# Encoder_Fin_-_MCU.net
KiCad netlist of a schematic drawn in Altium Designer
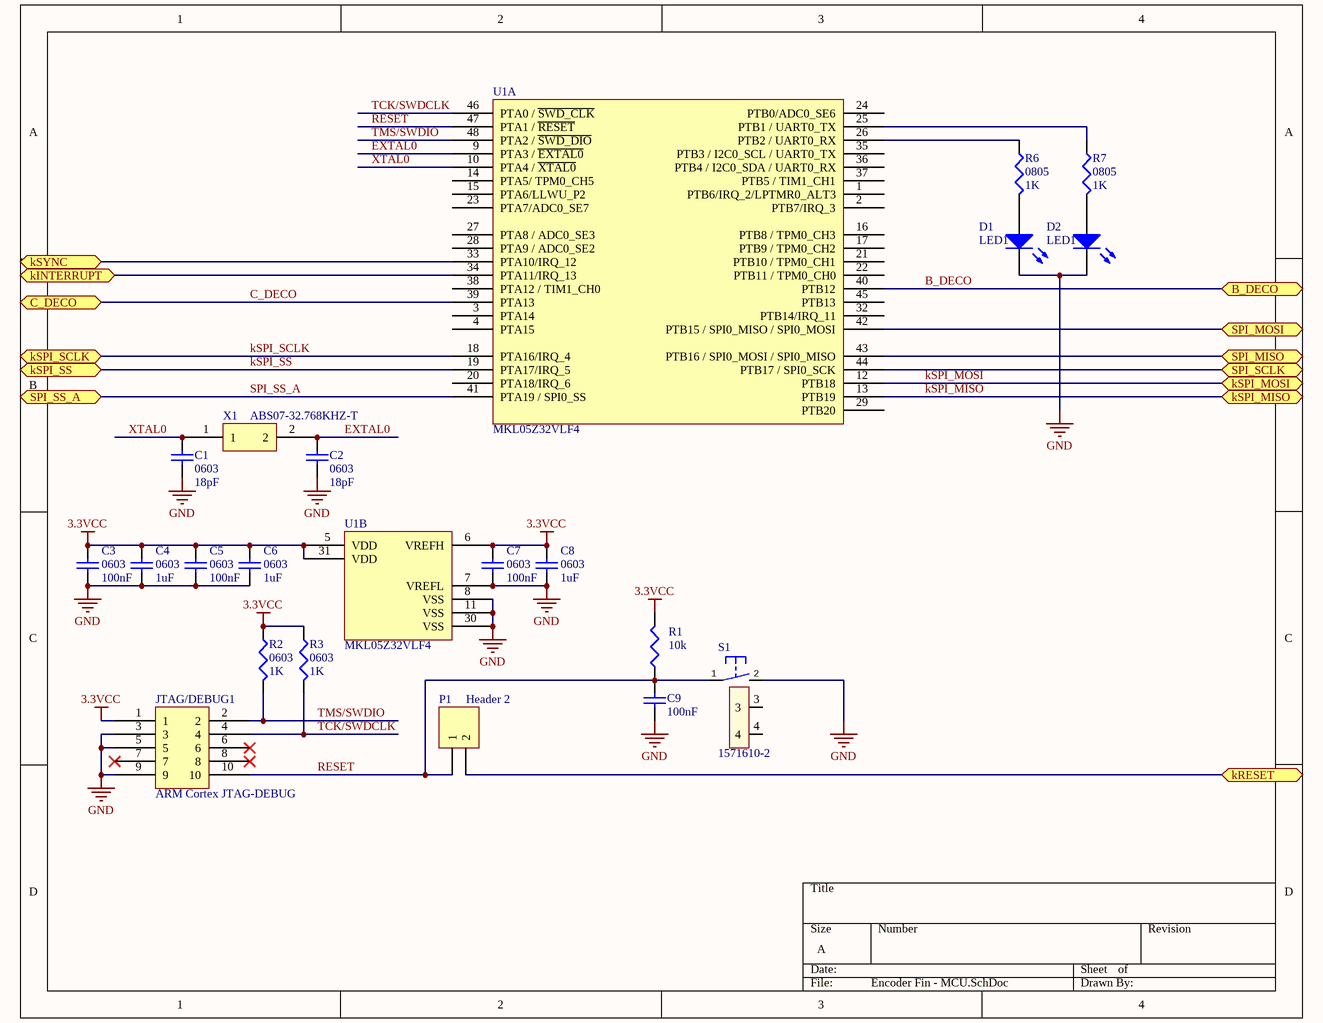
[diagram p0: Encoder Fin - MCU.SchDoc]

(export (version "E")
  (design (tool "Eeschema 10.0.6"))
  (components
    (comp (ref "C1")
      (value "0603")
      (footprint "1608[0603]")
      (description "Capacitor (Semiconductor SIM Model)")
      (fields (field (name "ALTIUM_VALUE") "18pF") (field (name "PUBLISHER") "Altium Limited"))
      (libsource (lib "Miscellaneous Devices") (part "Cap Semi"))
    )
    (comp (ref "C2")
      (value "0603")
      (footprint "1608[0603]")
      (description "Capacitor (Semiconductor SIM Model)")
      (fields (field (name "ALTIUM_VALUE") "18pF") (field (name "PUBLISHER") "Altium Limited"))
      (libsource (lib "Miscellaneous Devices") (part "Cap Semi"))
    )
    (comp (ref "C3")
      (value "0603")
      (footprint "1608[0603]")
      (description "Capacitor (Semiconductor SIM Model)")
      (fields (field (name "ALTIUM_VALUE") "100nF") (field (name "PUBLISHER") "Altium Limited"))
      (libsource (lib "Miscellaneous Devices") (part "Cap Semi"))
    )
    (comp (ref "C4")
      (value "0603")
      (footprint "1608[0603]")
      (description "Capacitor (Semiconductor SIM Model)")
      (fields (field (name "ALTIUM_VALUE") "1uF") (field (name "PUBLISHER") "Altium Limited"))
      (libsource (lib "Miscellaneous Devices") (part "Cap Semi"))
    )
    (comp (ref "C5")
      (value "0603")
      (footprint "1608[0603]")
      (description "Capacitor (Semiconductor SIM Model)")
      (fields (field (name "ALTIUM_VALUE") "100nF") (field (name "PUBLISHER") "Altium Limited"))
      (libsource (lib "Miscellaneous Devices") (part "Cap Semi"))
    )
    (comp (ref "C6")
      (value "0603")
      (footprint "1608[0603]")
      (description "Capacitor (Semiconductor SIM Model)")
      (fields (field (name "ALTIUM_VALUE") "1uF") (field (name "PUBLISHER") "Altium Limited"))
      (libsource (lib "Miscellaneous Devices") (part "Cap Semi"))
    )
    (comp (ref "C7")
      (value "0603")
      (footprint "1608[0603]")
      (description "Capacitor (Semiconductor SIM Model)")
      (fields (field (name "ALTIUM_VALUE") "100nF") (field (name "PUBLISHER") "Altium Limited"))
      (libsource (lib "Miscellaneous Devices") (part "Cap Semi"))
    )
    (comp (ref "C8")
      (value "0603")
      (footprint "1608[0603]")
      (description "Capacitor (Semiconductor SIM Model)")
      (fields (field (name "ALTIUM_VALUE") "1uF") (field (name "PUBLISHER") "Altium Limited"))
      (libsource (lib "Miscellaneous Devices") (part "Cap Semi"))
    )
    (comp (ref "C9")
      (value "100nF")
      (footprint "1608[0603]")
      (description "Capacitor (Semiconductor SIM Model)")
      (fields (field (name "Comment") "Cap Semi") (field (name "PUBLISHER") "Altium Limited"))
      (libsource (lib "Miscellaneous Devices") (part "Cap Semi"))
    )
    (comp (ref "D1")
      (value "LED1")
      (footprint "SM 0805 polarized")
      (description "Typical RED GaAs LED")
      (fields (field (name "PUBLISHER") "Altium Limited"))
      (libsource (lib "Miscellaneous Devices") (part "LED1"))
    )
    (comp (ref "D2")
      (value "LED1")
      (footprint "SM 0805 polarized")
      (description "Typical RED GaAs LED")
      (fields (field (name "PUBLISHER") "Altium Limited"))
      (libsource (lib "Miscellaneous Devices") (part "LED1"))
    )
    (comp (ref "JTAG/DEBUG1")
      (value "ARM Cortex JTAG-DEBUG")
      (footprint "FTSH-105-XX-X-DV")
      (libsource (lib "Adams Altium Library") (part "ARM Cortex JTAG-DEBUG Header"))
    )
    (comp (ref "P1")
      (value "Header 2")
      (footprint "HDR1X2")
      (description "Header, 2-Pin")
      (fields (field (name "PUBLISHER") "Altium Limited"))
      (libsource (lib "Miscellaneous Connectors") (part "Header 2"))
    )
    (comp (ref "R1")
      (value "10k")
      (footprint "J1-0603")
      (description "Resistor")
      (fields (field (name "Comment") "Res3") (field (name "PUBLISHER") "Altium Limited"))
      (libsource (lib "Miscellaneous Devices") (part "Res3"))
    )
    (comp (ref "R2")
      (value "0603")
      (footprint "J1-0603")
      (description "Resistor")
      (fields (field (name "ALTIUM_VALUE") "1K") (field (name "PUBLISHER") "Altium Limited"))
      (libsource (lib "Miscellaneous Devices") (part "Res3"))
    )
    (comp (ref "R3")
      (value "0603")
      (footprint "J1-0603")
      (description "Resistor")
      (fields (field (name "ALTIUM_VALUE") "1K") (field (name "PUBLISHER") "Altium Limited"))
      (libsource (lib "Miscellaneous Devices") (part "Res3"))
    )
    (comp (ref "R6")
      (value "0805")
      (footprint "SM 0805 - gap trimmed")
      (description "Resistor")
      (fields (field (name "ALTIUM_VALUE") "1K") (field (name "PUBLISHER") "Altium Limited"))
      (libsource (lib "Miscellaneous Devices") (part "Res3"))
    )
    (comp (ref "R7")
      (value "0805")
      (footprint "SM 0805 - gap trimmed")
      (description "Resistor")
      (fields (field (name "ALTIUM_VALUE") "1K") (field (name "PUBLISHER") "Altium Limited"))
      (libsource (lib "Miscellaneous Devices") (part "Res3"))
    )
    (comp (ref "S1")
      (value "1571610-2")
      (footprint "B3F-31XX")
      (description "SWTCH Momentary Washable")
      (fields
        (field (name "MANUFACTURER") "Omron")
        (field (name "MANUFACTURER_1") "TE")
        (field (name "PUBLISHER") "UltiMachine")
      )
      (libsource (lib "ZMBo Schematic Library") (part "1571610-2_1"))
    )
    (comp (ref "U1")
      (value "MKL05Z32VLF4")
      (footprint "MKL05Z32VLF4")
      (description "ARM Cortex M0+")
      (libsource (lib "ExtruderFinLib") (part "MKL05Z32VLF4"))
    )
    (comp (ref "X1")
      (value "ABS07-32.768KHZ-T")
      (footprint "ABS07-32.768KHZ-T")
      (description "ABS07-32.768KHZ-T RTC Crystal Oscillator")
      (libsource (lib "Adams Altium Library") (part "ABS07-32.768KHZ-T"))
    )
  )
  (nets
    (net (code "1") (name "/B_DECO") (class "Default")
      (node (ref "U1") (pin "40") (pinfunction "PTB12_40") (pintype "passive"))
    )
    (net (code "2") (name "/C_DECO") (class "Default")
      (node (ref "U1") (pin "39") (pinfunction "PTA13_39") (pintype "passive"))
    )
    (net (code "3") (name "/EXTAL0") (class "Default")
      (node (ref "C2") (pin "1") (pinfunction "1_1") (pintype "passive"))
      (node (ref "U1") (pin "9") (pinfunction "PTA3_/_~{EXTAL0}_9") (pintype "passive"))
      (node (ref "X1") (pin "2") (pinfunction "2_2") (pintype "passive"))
    )
    (net (code "4") (name "/RESET") (class "Default")
      (node (ref "C9") (pin "2") (pinfunction "2_2") (pintype "passive"))
      (node (ref "JTAG/DEBUG1") (pin "10") (pinfunction "10_10") (pintype "passive"))
      (node (ref "P1") (pin "1") (pinfunction "1_1") (pintype "passive"))
      (node (ref "R1") (pin "1") (pinfunction "1_1") (pintype "passive"))
      (node (ref "S1") (pin "1") (pinfunction "P_1") (pintype "passive"))
      (node (ref "U1") (pin "47") (pinfunction "PTA1_/_~{RESET}_47") (pintype "passive"))
    )
    (net (code "5") (name "/SPI_MISO") (class "Default")
      (node (ref "U1") (pin "43") (pinfunction "PTB16_/_SPI0_MOSI_43") (pintype "passive"))
    )
    (net (code "6") (name "/SPI_MOSI") (class "Default")
      (node (ref "U1") (pin "42") (pinfunction "PTB15_/_SPI0_MISO_42") (pintype "passive"))
    )
    (net (code "7") (name "/SPI_SCLK") (class "Default")
      (node (ref "U1") (pin "44") (pinfunction "PTB17_/_SPI0_SCK_44") (pintype "passive"))
    )
    (net (code "8") (name "/SPI_SS_A") (class "Default")
      (node (ref "U1") (pin "41") (pinfunction "PTA19_/_SPI0_SS_41") (pintype "passive"))
    )
    (net (code "9") (name "/TCK{slash}SWDCLK") (class "Default")
      (node (ref "JTAG/DEBUG1") (pin "4") (pinfunction "4_4") (pintype "passive"))
      (node (ref "R3") (pin "2") (pinfunction "2_2") (pintype "passive"))
      (node (ref "U1") (pin "46") (pinfunction "PTA0_/_~{SWD_CLK}_46") (pintype "passive"))
    )
    (net (code "10") (name "/TMS{slash}SWDIO") (class "Default")
      (node (ref "JTAG/DEBUG1") (pin "2") (pinfunction "2_2") (pintype "passive"))
      (node (ref "R2") (pin "2") (pinfunction "2_2") (pintype "passive"))
      (node (ref "U1") (pin "48") (pinfunction "PTA2_/_~{SWD_DIO}_48") (pintype "passive"))
    )
    (net (code "11") (name "/XTAL0") (class "Default")
      (node (ref "C1") (pin "1") (pinfunction "1_1") (pintype "passive"))
      (node (ref "U1") (pin "10") (pinfunction "PTA4_/_~{XTAL0}_10") (pintype "passive"))
      (node (ref "X1") (pin "1") (pinfunction "1_1") (pintype "passive"))
    )
    (net (code "12") (name "/kINTERRUPT") (class "Default")
      (node (ref "U1") (pin "34") (pinfunction "PTA11/IRQ_13_34") (pintype "passive"))
    )
    (net (code "13") (name "/kRESET") (class "Default")
      (node (ref "P1") (pin "2") (pinfunction "2_2") (pintype "passive"))
    )
    (net (code "14") (name "/kSPI_MISO") (class "Default")
      (node (ref "U1") (pin "13") (pinfunction "PTB19_13") (pintype "passive"))
    )
    (net (code "15") (name "/kSPI_MOSI") (class "Default")
      (node (ref "U1") (pin "12") (pinfunction "PTB18_12") (pintype "passive"))
    )
    (net (code "16") (name "/kSPI_SCLK") (class "Default")
      (node (ref "U1") (pin "18") (pinfunction "PTA16/IRQ_4_18") (pintype "passive"))
    )
    (net (code "17") (name "/kSPI_SS") (class "Default")
      (node (ref "U1") (pin "19") (pinfunction "PTA17/IRQ_5_19") (pintype "passive"))
    )
    (net (code "18") (name "/kSYNC") (class "Default")
      (node (ref "U1") (pin "33") (pinfunction "PTA10/IRQ_12_33") (pintype "passive"))
    )
    (net (code "19") (name "3.3VCC") (class "Default")
      (node (ref "C3") (pin "2") (pinfunction "2_2") (pintype "passive"))
      (node (ref "C4") (pin "2") (pinfunction "2_2") (pintype "passive"))
      (node (ref "C5") (pin "2") (pinfunction "2_2") (pintype "passive"))
      (node (ref "C6") (pin "2") (pinfunction "2_2") (pintype "passive"))
      (node (ref "C7") (pin "1") (pinfunction "1_1") (pintype "passive"))
      (node (ref "C8") (pin "1") (pinfunction "1_1") (pintype "passive"))
      (node (ref "JTAG/DEBUG1") (pin "1") (pinfunction "1_1") (pintype "passive"))
      (node (ref "R1") (pin "2") (pinfunction "2_2") (pintype "passive"))
      (node (ref "R2") (pin "1") (pinfunction "1_1") (pintype "passive"))
      (node (ref "R3") (pin "1") (pinfunction "1_1") (pintype "passive"))
      (node (ref "U1") (pin "31") (pinfunction "VDD_31") (pintype "passive"))
      (node (ref "U1") (pin "5") (pinfunction "VDD_5") (pintype "passive"))
      (node (ref "U1") (pin "6") (pinfunction "VREFH_6") (pintype "passive"))
    )
    (net (code "20") (name "GND") (class "Default")
      (node (ref "C1") (pin "2") (pinfunction "2_2") (pintype "passive"))
      (node (ref "C2") (pin "2") (pinfunction "2_2") (pintype "passive"))
      (node (ref "C3") (pin "1") (pinfunction "1_1") (pintype "passive"))
      (node (ref "C4") (pin "1") (pinfunction "1_1") (pintype "passive"))
      (node (ref "C5") (pin "1") (pinfunction "1_1") (pintype "passive"))
      (node (ref "C6") (pin "1") (pinfunction "1_1") (pintype "passive"))
      (node (ref "C7") (pin "2") (pinfunction "2_2") (pintype "passive"))
      (node (ref "C8") (pin "2") (pinfunction "2_2") (pintype "passive"))
      (node (ref "C9") (pin "1") (pinfunction "1_1") (pintype "passive"))
      (node (ref "D1") (pin "1") (pinfunction "A_1") (pintype "passive"))
      (node (ref "D2") (pin "1") (pinfunction "A_1") (pintype "passive"))
      (node (ref "JTAG/DEBUG1") (pin "3") (pinfunction "3_3") (pintype "passive"))
      (node (ref "JTAG/DEBUG1") (pin "5") (pinfunction "5_5") (pintype "passive"))
      (node (ref "JTAG/DEBUG1") (pin "9") (pinfunction "9_9") (pintype "passive"))
      (node (ref "S1") (pin "2") (pinfunction "S_2") (pintype "passive"))
      (node (ref "U1") (pin "11") (pinfunction "VSS_11") (pintype "passive"))
      (node (ref "U1") (pin "30") (pinfunction "VSS_30") (pintype "passive"))
      (node (ref "U1") (pin "7") (pinfunction "VREFL_7") (pintype "passive"))
      (node (ref "U1") (pin "8") (pinfunction "VSS_8") (pintype "passive"))
    )
    (net (code "21") (name "Net-(D1-K)") (class "Default")
      (node (ref "D1") (pin "2") (pinfunction "K_2") (pintype "passive"))
      (node (ref "R6") (pin "2") (pinfunction "2_2") (pintype "passive"))
    )
    (net (code "22") (name "Net-(D2-K)") (class "Default")
      (node (ref "D2") (pin "2") (pinfunction "K_2") (pintype "passive"))
      (node (ref "R7") (pin "2") (pinfunction "2_2") (pintype "passive"))
    )
    (net (code "23") (name "Net-(U1A-PTB1_{slash}_UART0_TX)") (class "Default")
      (node (ref "R7") (pin "1") (pinfunction "1_1") (pintype "passive"))
      (node (ref "U1") (pin "25") (pinfunction "PTB1_/_UART0_TX_25") (pintype "passive"))
    )
    (net (code "24") (name "Net-(U1A-PTB2_{slash}_UART0_RX)") (class "Default")
      (node (ref "R6") (pin "1") (pinfunction "1_1") (pintype "passive"))
      (node (ref "U1") (pin "26") (pinfunction "PTB2_/_UART0_RX_26") (pintype "passive"))
    )
    (net (code "25") (name "unconnected-(JTAG/DEBUG1-Pad6)") (class "Default")
      (node (ref "JTAG/DEBUG1") (pin "6") (pinfunction "6_6") (pintype "passive+no_connect"))
    )
    (net (code "26") (name "unconnected-(JTAG/DEBUG1-Pad7)") (class "Default")
      (node (ref "JTAG/DEBUG1") (pin "7") (pinfunction "7_7") (pintype "passive+no_connect"))
    )
    (net (code "27") (name "unconnected-(JTAG/DEBUG1-Pad8)") (class "Default")
      (node (ref "JTAG/DEBUG1") (pin "8") (pinfunction "8_8") (pintype "passive+no_connect"))
    )
    (net (code "28") (name "unconnected-(S1-Pad3)") (class "Default")
      (node (ref "S1") (pin "3") (pinfunction "3_3") (pintype "power_in"))
    )
    (net (code "29") (name "unconnected-(S1-Pad4)") (class "Default")
      (node (ref "S1") (pin "4") (pinfunction "4_4") (pintype "power_in"))
    )
    (net (code "30") (name "unconnected-(U1A-PTA5{slash}LLWU_P{slash}RTC_CLK_IN-Pad14)") (class "Default")
      (node (ref "U1") (pin "14") (pinfunction "PTA5/LLWU_P/RTC_CLK_IN_14") (pintype "passive"))
    )
    (net (code "31") (name "unconnected-(U1A-PTA6{slash}LLWU_P2-Pad15)") (class "Default")
      (node (ref "U1") (pin "15") (pinfunction "PTA6/LLWU_P2_15") (pintype "passive"))
    )
    (net (code "32") (name "unconnected-(U1A-PTA7{slash}IRQ_7{slash}LLWU_P3-Pad23)") (class "Default")
      (node (ref "U1") (pin "23") (pinfunction "PTA7/IRQ_7/LLWU_P3_23") (pintype "passive"))
    )
    (net (code "33") (name "unconnected-(U1A-PTA8_{slash}_ADC0_SE3-Pad27)") (class "Default")
      (node (ref "U1") (pin "27") (pinfunction "PTA8_/_ADC0_SE3_27") (pintype "passive"))
    )
    (net (code "34") (name "unconnected-(U1A-PTA9_{slash}_ADC0_SE2-Pad28)") (class "Default")
      (node (ref "U1") (pin "28") (pinfunction "PTA9_/_ADC0_SE2_28") (pintype "passive"))
    )
    (net (code "35") (name "unconnected-(U1A-PTA12_{slash}_TIM1_CH0-Pad38)") (class "Default")
      (node (ref "U1") (pin "38") (pinfunction "PTA12_/_TIM1_CH0_38") (pintype "passive"))
    )
    (net (code "36") (name "unconnected-(U1A-PTA14-Pad3)") (class "Default")
      (node (ref "U1") (pin "3") (pinfunction "PTA14_3") (pintype "passive"))
    )
    (net (code "37") (name "unconnected-(U1A-PTA15-Pad4)") (class "Default")
      (node (ref "U1") (pin "4") (pinfunction "PTA15_4") (pintype "passive"))
    )
    (net (code "38") (name "unconnected-(U1A-PTA18{slash}IRQ_6-Pad20)") (class "Default")
      (node (ref "U1") (pin "20") (pinfunction "PTA18/IRQ_6_20") (pintype "passive"))
    )
    (net (code "39") (name "unconnected-(U1A-PTB0{slash}IRQ_8{slash}LLWU_P4-Pad24)") (class "Default")
      (node (ref "U1") (pin "24") (pinfunction "PTB0/IRQ_8/LLWU_P4_24") (pintype "passive"))
    )
    (net (code "40") (name "unconnected-(U1A-PTB3_{slash}_I2C0_SCL_{slash}_UART0_TX-Pad35)") (class "Default")
      (node (ref "U1") (pin "35") (pinfunction "PTB3_/_I2C0_SCL_/_UART0_TX_35") (pintype "passive"))
    )
    (net (code "41") (name "unconnected-(U1A-PTB4_{slash}_I2C0_SDA_{slash}_UART0_RX-Pad36)") (class "Default")
      (node (ref "U1") (pin "36") (pinfunction "PTB4_/_I2C0_SDA_/_UART0_RX_36") (pintype "passive"))
    )
    (net (code "42") (name "unconnected-(U1A-PTB5_{slash}_TIM1_CH1-Pad37)") (class "Default")
      (node (ref "U1") (pin "37") (pinfunction "PTB5_/_TIM1_CH1_37") (pintype "passive"))
    )
    (net (code "43") (name "unconnected-(U1A-PTB6{slash}IRQ_2{slash}LPTMR0_ALT3-Pad1)") (class "Default")
      (node (ref "U1") (pin "1") (pinfunction "PTB6/IRQ_2/LPTMR0_ALT3_1") (pintype "passive"))
    )
    (net (code "44") (name "unconnected-(U1A-PTB7{slash}IRQ_3-Pad2)") (class "Default")
      (node (ref "U1") (pin "2") (pinfunction "PTB7/IRQ_3_2") (pintype "passive"))
    )
    (net (code "45") (name "unconnected-(U1A-PTB8_{slash}_TPM0_CH3-Pad16)") (class "Default")
      (node (ref "U1") (pin "16") (pinfunction "PTB8_/_TPM0_CH3_16") (pintype "passive"))
    )
    (net (code "46") (name "unconnected-(U1A-PTB9_{slash}_TPM0_CH2-Pad17)") (class "Default")
      (node (ref "U1") (pin "17") (pinfunction "PTB9_/_TPM0_CH2_17") (pintype "passive"))
    )
    (net (code "47") (name "unconnected-(U1A-PTB10_{slash}_TPM0_CH1-Pad21)") (class "Default")
      (node (ref "U1") (pin "21") (pinfunction "PTB10_/_TPM0_CH1_21") (pintype "passive"))
    )
    (net (code "48") (name "unconnected-(U1A-PTB11_{slash}_TPM0_CH0-Pad22)") (class "Default")
      (node (ref "U1") (pin "22") (pinfunction "PTB11_/_TPM0_CH0_22") (pintype "passive"))
    )
    (net (code "49") (name "unconnected-(U1A-PTB13-Pad45)") (class "Default")
      (node (ref "U1") (pin "45") (pinfunction "PTB13_45") (pintype "passive"))
    )
    (net (code "50") (name "unconnected-(U1A-PTB14{slash}IRQ_11-Pad32)") (class "Default")
      (node (ref "U1") (pin "32") (pinfunction "PTB14/IRQ_11_32") (pintype "passive"))
    )
    (net (code "51") (name "unconnected-(U1A-PTB20-Pad29)") (class "Default")
      (node (ref "U1") (pin "29") (pinfunction "PTB20_29") (pintype "passive"))
    )
  )
)
